# M121D.net
KiCad netlist of a schematic drawn in EAGLE
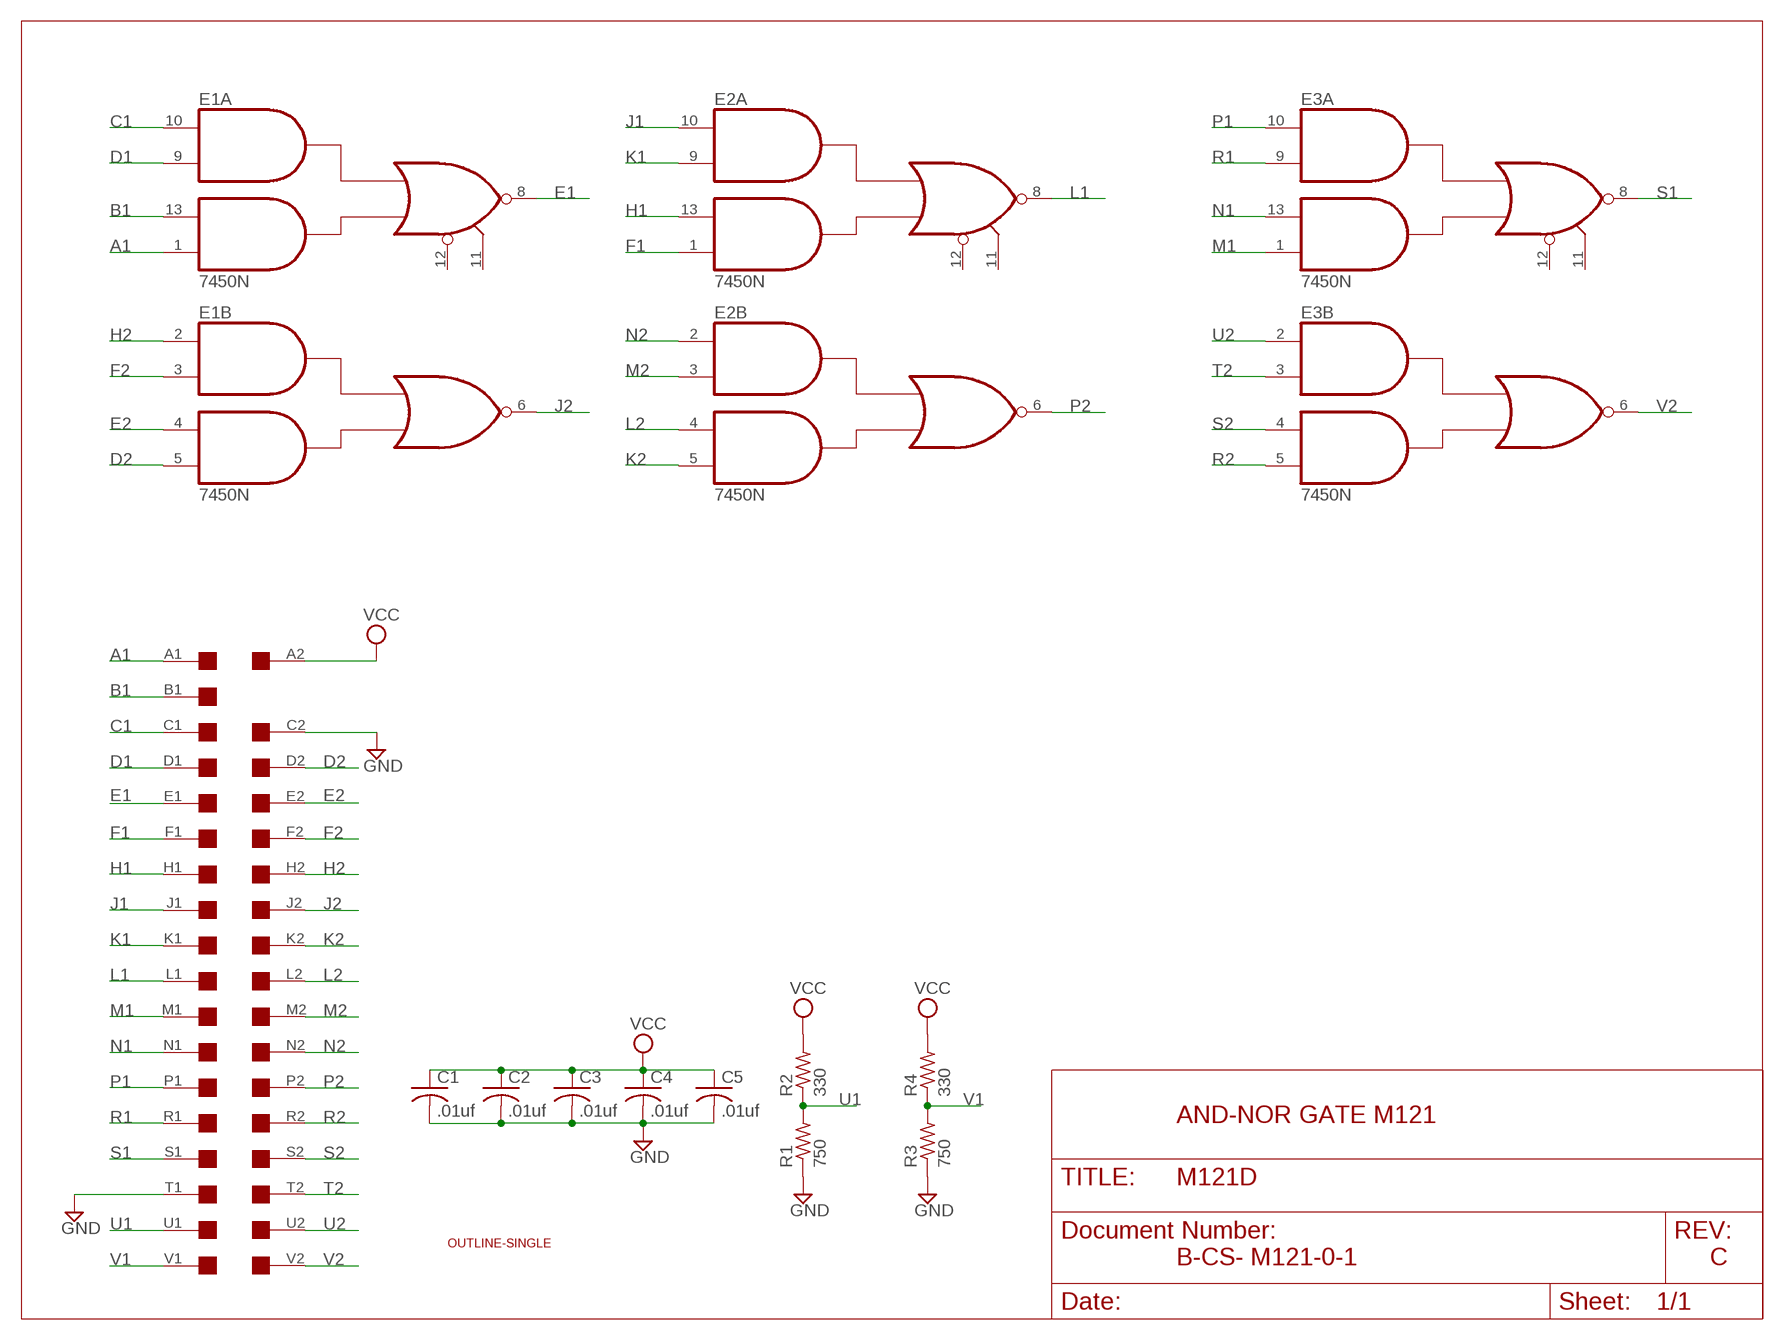
[diagram p0: schematic, sheet 1]

(export (version "E")
  (design (tool "Eeschema 10.0.6"))
  (components
    (comp (ref "C1")
      (value ".01uf")
      (footprint "eagle-import:C050-025X075")
      (libsource (lib "eagle-import") (part "C-US050-025X075"))
    )
    (comp (ref "C2")
      (value ".01uf")
      (footprint "eagle-import:C050-025X075")
      (libsource (lib "eagle-import") (part "C-US050-025X075"))
    )
    (comp (ref "C3")
      (value ".01uf")
      (footprint "eagle-import:C050-025X075")
      (libsource (lib "eagle-import") (part "C-US050-025X075"))
    )
    (comp (ref "C4")
      (value ".01uf")
      (footprint "eagle-import:C050-025X075")
      (libsource (lib "eagle-import") (part "C-US050-025X075"))
    )
    (comp (ref "C5")
      (value ".01uf")
      (footprint "eagle-import:C050-025X075")
      (libsource (lib "eagle-import") (part "C-US050-025X075"))
    )
    (comp (ref "E1")
      (value "7450N")
      (footprint "eagle-import:DIL14")
      (libsource (lib "eagle-import") (part "7450N"))
    )
    (comp (ref "E2")
      (value "7450N")
      (footprint "eagle-import:DIL14")
      (libsource (lib "eagle-import") (part "7450N"))
    )
    (comp (ref "E3")
      (value "7450N")
      (footprint "eagle-import:DIL14")
      (libsource (lib "eagle-import") (part "7450N"))
    )
    (comp (ref "R1")
      (value "750")
      (footprint "eagle-import:0207_10")
      (libsource (lib "eagle-import") (part "R-US_0207/10"))
    )
    (comp (ref "R2")
      (value "330")
      (footprint "eagle-import:0207_10")
      (libsource (lib "eagle-import") (part "R-US_0207/10"))
    )
    (comp (ref "R3")
      (value "750")
      (footprint "eagle-import:0207_10")
      (libsource (lib "eagle-import") (part "R-US_0207/10"))
    )
    (comp (ref "R4")
      (value "330")
      (footprint "eagle-import:0207_10")
      (libsource (lib "eagle-import") (part "R-US_0207/10"))
    )
    (comp (ref "U$1")
      (value "OUTLINE-SINGLE")
      (footprint "eagle-import:SINGLE")
      (libsource (lib "eagle-import") (part "OUTLINE-SINGLE"))
    )
    (comp (ref "U$4")
      (value "SINGLE")
      (footprint "eagle-import:EDGE-CON2")
      (libsource (lib "eagle-import") (part "SINGLE"))
    )
  )
  (nets
    (net (code "1") (name "/A1") (class "Default")
      (node (ref "E1") (pin "1") (pinfunction "I4_1") (pintype "input"))
      (node (ref "U$4") (pin "A1") (pinfunction "1_A1") (pintype "bidirectional"))
    )
    (net (code "2") (name "/B1") (class "Default")
      (node (ref "E1") (pin "13") (pinfunction "I3_13") (pintype "input"))
      (node (ref "U$4") (pin "B1") (pinfunction "1_B1") (pintype "bidirectional"))
    )
    (net (code "3") (name "/C1") (class "Default")
      (node (ref "E1") (pin "10") (pinfunction "I1_10") (pintype "input"))
      (node (ref "U$4") (pin "C1") (pinfunction "1_C1") (pintype "bidirectional"))
    )
    (net (code "4") (name "/D1") (class "Default")
      (node (ref "E1") (pin "9") (pinfunction "I2_9") (pintype "input"))
      (node (ref "U$4") (pin "D1") (pinfunction "1_D1") (pintype "bidirectional"))
    )
    (net (code "5") (name "/D2") (class "Default")
      (node (ref "E1") (pin "5") (pinfunction "I4_5") (pintype "input"))
      (node (ref "U$4") (pin "D2") (pinfunction "1_D2") (pintype "bidirectional"))
    )
    (net (code "6") (name "/E1") (class "Default")
      (node (ref "E1") (pin "8") (pinfunction "O_8") (pintype "output"))
      (node (ref "U$4") (pin "E1") (pinfunction "1_E1") (pintype "bidirectional"))
    )
    (net (code "7") (name "/E2") (class "Default")
      (node (ref "E1") (pin "4") (pinfunction "I3_4") (pintype "input"))
      (node (ref "U$4") (pin "E2") (pinfunction "1_E2") (pintype "bidirectional"))
    )
    (net (code "8") (name "/F1") (class "Default")
      (node (ref "E2") (pin "1") (pinfunction "I4_1") (pintype "input"))
      (node (ref "U$4") (pin "F1") (pinfunction "1_F1") (pintype "bidirectional"))
    )
    (net (code "9") (name "/F2") (class "Default")
      (node (ref "E1") (pin "3") (pinfunction "I2_3") (pintype "input"))
      (node (ref "U$4") (pin "F2") (pinfunction "1_F2") (pintype "bidirectional"))
    )
    (net (code "10") (name "/H1") (class "Default")
      (node (ref "E2") (pin "13") (pinfunction "I3_13") (pintype "input"))
      (node (ref "U$4") (pin "H1") (pinfunction "1_H1") (pintype "bidirectional"))
    )
    (net (code "11") (name "/H2") (class "Default")
      (node (ref "E1") (pin "2") (pinfunction "I1_2") (pintype "input"))
      (node (ref "U$4") (pin "H2") (pinfunction "1_H2") (pintype "bidirectional"))
    )
    (net (code "12") (name "/J1") (class "Default")
      (node (ref "E2") (pin "10") (pinfunction "I1_10") (pintype "input"))
      (node (ref "U$4") (pin "J1") (pinfunction "1_J1") (pintype "bidirectional"))
    )
    (net (code "13") (name "/J2") (class "Default")
      (node (ref "E1") (pin "6") (pinfunction "O_6") (pintype "output"))
      (node (ref "U$4") (pin "J2") (pinfunction "1_J2") (pintype "bidirectional"))
    )
    (net (code "14") (name "/K1") (class "Default")
      (node (ref "E2") (pin "9") (pinfunction "I2_9") (pintype "input"))
      (node (ref "U$4") (pin "K1") (pinfunction "1_K1") (pintype "bidirectional"))
    )
    (net (code "15") (name "/K2") (class "Default")
      (node (ref "E2") (pin "5") (pinfunction "I4_5") (pintype "input"))
      (node (ref "U$4") (pin "K2") (pinfunction "1_K2") (pintype "bidirectional"))
    )
    (net (code "16") (name "/L1") (class "Default")
      (node (ref "E2") (pin "8") (pinfunction "O_8") (pintype "output"))
      (node (ref "U$4") (pin "L1") (pinfunction "1_L1") (pintype "bidirectional"))
    )
    (net (code "17") (name "/L2") (class "Default")
      (node (ref "E2") (pin "4") (pinfunction "I3_4") (pintype "input"))
      (node (ref "U$4") (pin "L2") (pinfunction "1_L2") (pintype "bidirectional"))
    )
    (net (code "18") (name "/M1") (class "Default")
      (node (ref "E3") (pin "1") (pinfunction "I4_1") (pintype "input"))
      (node (ref "U$4") (pin "M1") (pinfunction "1_M1") (pintype "bidirectional"))
    )
    (net (code "19") (name "/M2") (class "Default")
      (node (ref "E2") (pin "3") (pinfunction "I2_3") (pintype "input"))
      (node (ref "U$4") (pin "M2") (pinfunction "1_M2") (pintype "bidirectional"))
    )
    (net (code "20") (name "/N1") (class "Default")
      (node (ref "E3") (pin "13") (pinfunction "I3_13") (pintype "input"))
      (node (ref "U$4") (pin "N1") (pinfunction "1_N1") (pintype "bidirectional"))
    )
    (net (code "21") (name "/N2") (class "Default")
      (node (ref "E2") (pin "2") (pinfunction "I1_2") (pintype "input"))
      (node (ref "U$4") (pin "N2") (pinfunction "1_N2") (pintype "bidirectional"))
    )
    (net (code "22") (name "/P1") (class "Default")
      (node (ref "E3") (pin "10") (pinfunction "I1_10") (pintype "input"))
      (node (ref "U$4") (pin "P1") (pinfunction "1_P1") (pintype "bidirectional"))
    )
    (net (code "23") (name "/P2") (class "Default")
      (node (ref "E2") (pin "6") (pinfunction "O_6") (pintype "output"))
      (node (ref "U$4") (pin "P2") (pinfunction "1_P2") (pintype "bidirectional"))
    )
    (net (code "24") (name "/R1") (class "Default")
      (node (ref "E3") (pin "9") (pinfunction "I2_9") (pintype "input"))
      (node (ref "U$4") (pin "R1") (pinfunction "1_R1") (pintype "bidirectional"))
    )
    (net (code "25") (name "/R2") (class "Default")
      (node (ref "E3") (pin "5") (pinfunction "I4_5") (pintype "input"))
      (node (ref "U$4") (pin "R2") (pinfunction "1_R2") (pintype "bidirectional"))
    )
    (net (code "26") (name "/S1") (class "Default")
      (node (ref "E3") (pin "8") (pinfunction "O_8") (pintype "output"))
      (node (ref "U$4") (pin "S1") (pinfunction "1_S1") (pintype "bidirectional"))
    )
    (net (code "27") (name "/S2") (class "Default")
      (node (ref "E3") (pin "4") (pinfunction "I3_4") (pintype "input"))
      (node (ref "U$4") (pin "S2") (pinfunction "1_S2") (pintype "bidirectional"))
    )
    (net (code "28") (name "/T2") (class "Default")
      (node (ref "E3") (pin "3") (pinfunction "I2_3") (pintype "input"))
      (node (ref "U$4") (pin "T2") (pinfunction "1_T2") (pintype "bidirectional"))
    )
    (net (code "29") (name "/U1") (class "Default")
      (node (ref "R1") (pin "2") (pinfunction "2_2") (pintype "passive"))
      (node (ref "R2") (pin "1") (pinfunction "1_1") (pintype "passive"))
      (node (ref "U$4") (pin "U1") (pinfunction "1_U1") (pintype "bidirectional"))
    )
    (net (code "30") (name "/U2") (class "Default")
      (node (ref "E3") (pin "2") (pinfunction "I1_2") (pintype "input"))
      (node (ref "U$4") (pin "U2") (pinfunction "1_U2") (pintype "bidirectional"))
    )
    (net (code "31") (name "/V1") (class "Default")
      (node (ref "R3") (pin "2") (pinfunction "2_2") (pintype "passive"))
      (node (ref "R4") (pin "1") (pinfunction "1_1") (pintype "passive"))
      (node (ref "U$4") (pin "V1") (pinfunction "1_V1") (pintype "bidirectional"))
    )
    (net (code "32") (name "/V2") (class "Default")
      (node (ref "E3") (pin "6") (pinfunction "O_6") (pintype "output"))
      (node (ref "U$4") (pin "V2") (pinfunction "1_V2") (pintype "bidirectional"))
    )
    (net (code "33") (name "GND") (class "Default")
      (node (ref "C1") (pin "2") (pinfunction "2_2") (pintype "passive"))
      (node (ref "C2") (pin "2") (pinfunction "2_2") (pintype "passive"))
      (node (ref "C3") (pin "2") (pinfunction "2_2") (pintype "passive"))
      (node (ref "C4") (pin "2") (pinfunction "2_2") (pintype "passive"))
      (node (ref "C5") (pin "2") (pinfunction "2_2") (pintype "passive"))
      (node (ref "R1") (pin "1") (pinfunction "1_1") (pintype "passive"))
      (node (ref "R3") (pin "1") (pinfunction "1_1") (pintype "passive"))
      (node (ref "U$4") (pin "C2") (pinfunction "1_C2") (pintype "bidirectional"))
      (node (ref "U$4") (pin "T1") (pinfunction "1_T1") (pintype "bidirectional"))
    )
    (net (code "34") (name "VCC") (class "Default")
      (node (ref "C1") (pin "1") (pinfunction "1_1") (pintype "passive"))
      (node (ref "C2") (pin "1") (pinfunction "1_1") (pintype "passive"))
      (node (ref "C3") (pin "1") (pinfunction "1_1") (pintype "passive"))
      (node (ref "C4") (pin "1") (pinfunction "1_1") (pintype "passive"))
      (node (ref "C5") (pin "1") (pinfunction "1_1") (pintype "passive"))
      (node (ref "R2") (pin "2") (pinfunction "2_2") (pintype "passive"))
      (node (ref "R4") (pin "2") (pinfunction "2_2") (pintype "passive"))
      (node (ref "U$4") (pin "A2") (pinfunction "1_A2") (pintype "bidirectional"))
    )
    (net (code "35") (name "unconnected-(E1A-I5-Pad12)") (class "Default")
      (node (ref "E1") (pin "12") (pinfunction "I5_12") (pintype "passive"))
    )
    (net (code "36") (name "unconnected-(E1A-I6-Pad11)") (class "Default")
      (node (ref "E1") (pin "11") (pinfunction "I6_11") (pintype "passive"))
    )
    (net (code "37") (name "unconnected-(E2A-I5-Pad12)") (class "Default")
      (node (ref "E2") (pin "12") (pinfunction "I5_12") (pintype "passive"))
    )
    (net (code "38") (name "unconnected-(E2A-I6-Pad11)") (class "Default")
      (node (ref "E2") (pin "11") (pinfunction "I6_11") (pintype "passive"))
    )
    (net (code "39") (name "unconnected-(E3A-I5-Pad12)") (class "Default")
      (node (ref "E3") (pin "12") (pinfunction "I5_12") (pintype "passive"))
    )
    (net (code "40") (name "unconnected-(E3A-I6-Pad11)") (class "Default")
      (node (ref "E3") (pin "11") (pinfunction "I6_11") (pintype "passive"))
    )
  )
)
